# MODELO_TRANSFORMADOR.net
KiCad netlist of a schematic drawn in Altium Designer
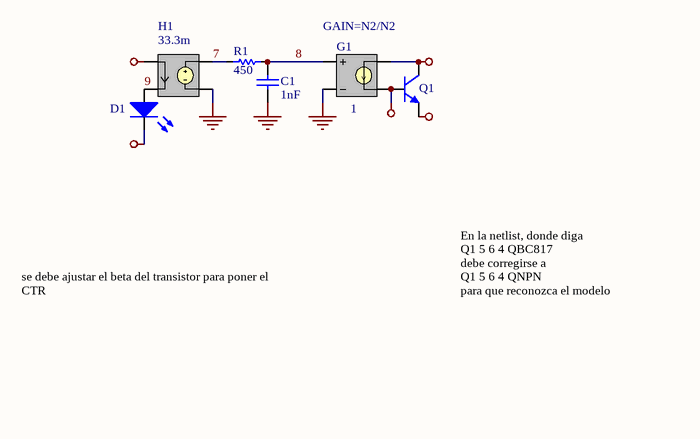
[diagram p0: MODELO TRANSFORMADOR.SCHDOC]

(export (version "E")
  (design (tool "Eeschema 10.0.6"))
  (components
    (comp (ref "C1")
      (value "1nF")
      (footprint "0805")
      (description "Capacitor")
      (fields (field (name "VOLTAGE") "50V") (field (name "Comment") "Cap"))
      (libsource (lib "FEDE") (part "Cap"))
    )
    (comp (ref "D1")
      (value "LED")
      (footprint "LED3mm")
      (description "Led")
      (libsource (lib "FEDE") (part "LED"))
    )
    (comp (ref "G1")
      (value "GSRC")
      (description "Voltage Controlled Current Source")
      (fields (field (name "GAIN") "1") (field (name "PUBLISHER") "Altium Limited"))
      (libsource (lib "Simulation Sources") (part "GSRC"))
    )
    (comp (ref "H1")
      (value "HSRC")
      (description "Current Controlled Voltage Source")
      (fields (field (name "GAIN") "33.3m") (field (name "PUBLISHER") "Altium Limited"))
      (libsource (lib "Simulation Sources") (part "HSRC"))
    )
    (comp (ref "Q1")
      (value "NPN")
      (footprint "SOT23")
      (description "NPN Bipolar Transistor")
      (libsource (lib "FEDE") (part "BC817"))
    )
    (comp (ref "R1")
      (value "450")
      (footprint "0805")
      (description "Resistor")
      (fields (field (name "POWER") "0.25W") (field (name "Comment") "Res"))
      (libsource (lib "FEDE") (part "Res"))
    )
  )
  (nets
    (net (code "1") (name "/7") (class "Default")
      (node (ref "H1") (pin "3") (pinfunction "N+_3") (pintype "passive"))
      (node (ref "R1") (pin "1") (pinfunction "1_1") (pintype "passive"))
    )
    (net (code "2") (name "/8") (class "Default")
      (node (ref "C1") (pin "1") (pinfunction "1_1") (pintype "passive"))
      (node (ref "G1") (pin "1") (pinfunction "NC+_1") (pintype "passive"))
      (node (ref "R1") (pin "2") (pinfunction "2_2") (pintype "passive"))
    )
    (net (code "3") (name "/9") (class "Default")
      (node (ref "D1") (pin "1") (pinfunction "A_1") (pintype "passive"))
      (node (ref "H1") (pin "2") (pinfunction "NC-_2") (pintype "passive"))
    )
    (net (code "4") (name "1") (class "Default")
      (node (ref "H1") (pin "1") (pinfunction "NC+_1") (pintype "passive"))
    )
    (net (code "5") (name "2") (class "Default")
      (node (ref "D1") (pin "2") (pinfunction "K_2") (pintype "passive"))
    )
    (net (code "6") (name "4") (class "Default")
      (node (ref "Q1") (pin "2") (pinfunction "E_2") (pintype "passive"))
    )
    (net (code "7") (name "5") (class "Default")
      (node (ref "G1") (pin "3") (pinfunction "N+_3") (pintype "passive"))
      (node (ref "Q1") (pin "3") (pinfunction "C_3") (pintype "passive"))
    )
    (net (code "8") (name "6") (class "Default")
      (node (ref "G1") (pin "4") (pinfunction "N-_4") (pintype "passive"))
      (node (ref "Q1") (pin "1") (pinfunction "B_1") (pintype "passive"))
    )
    (net (code "9") (name "GND") (class "Default")
      (node (ref "C1") (pin "2") (pinfunction "2_2") (pintype "passive"))
      (node (ref "G1") (pin "2") (pinfunction "NC-_2") (pintype "passive"))
      (node (ref "H1") (pin "4") (pinfunction "N-_4") (pintype "passive"))
    )
  )
)
